# spi_usb_iic.net
KiCad netlist of a schematic drawn in EasyEDA Pro
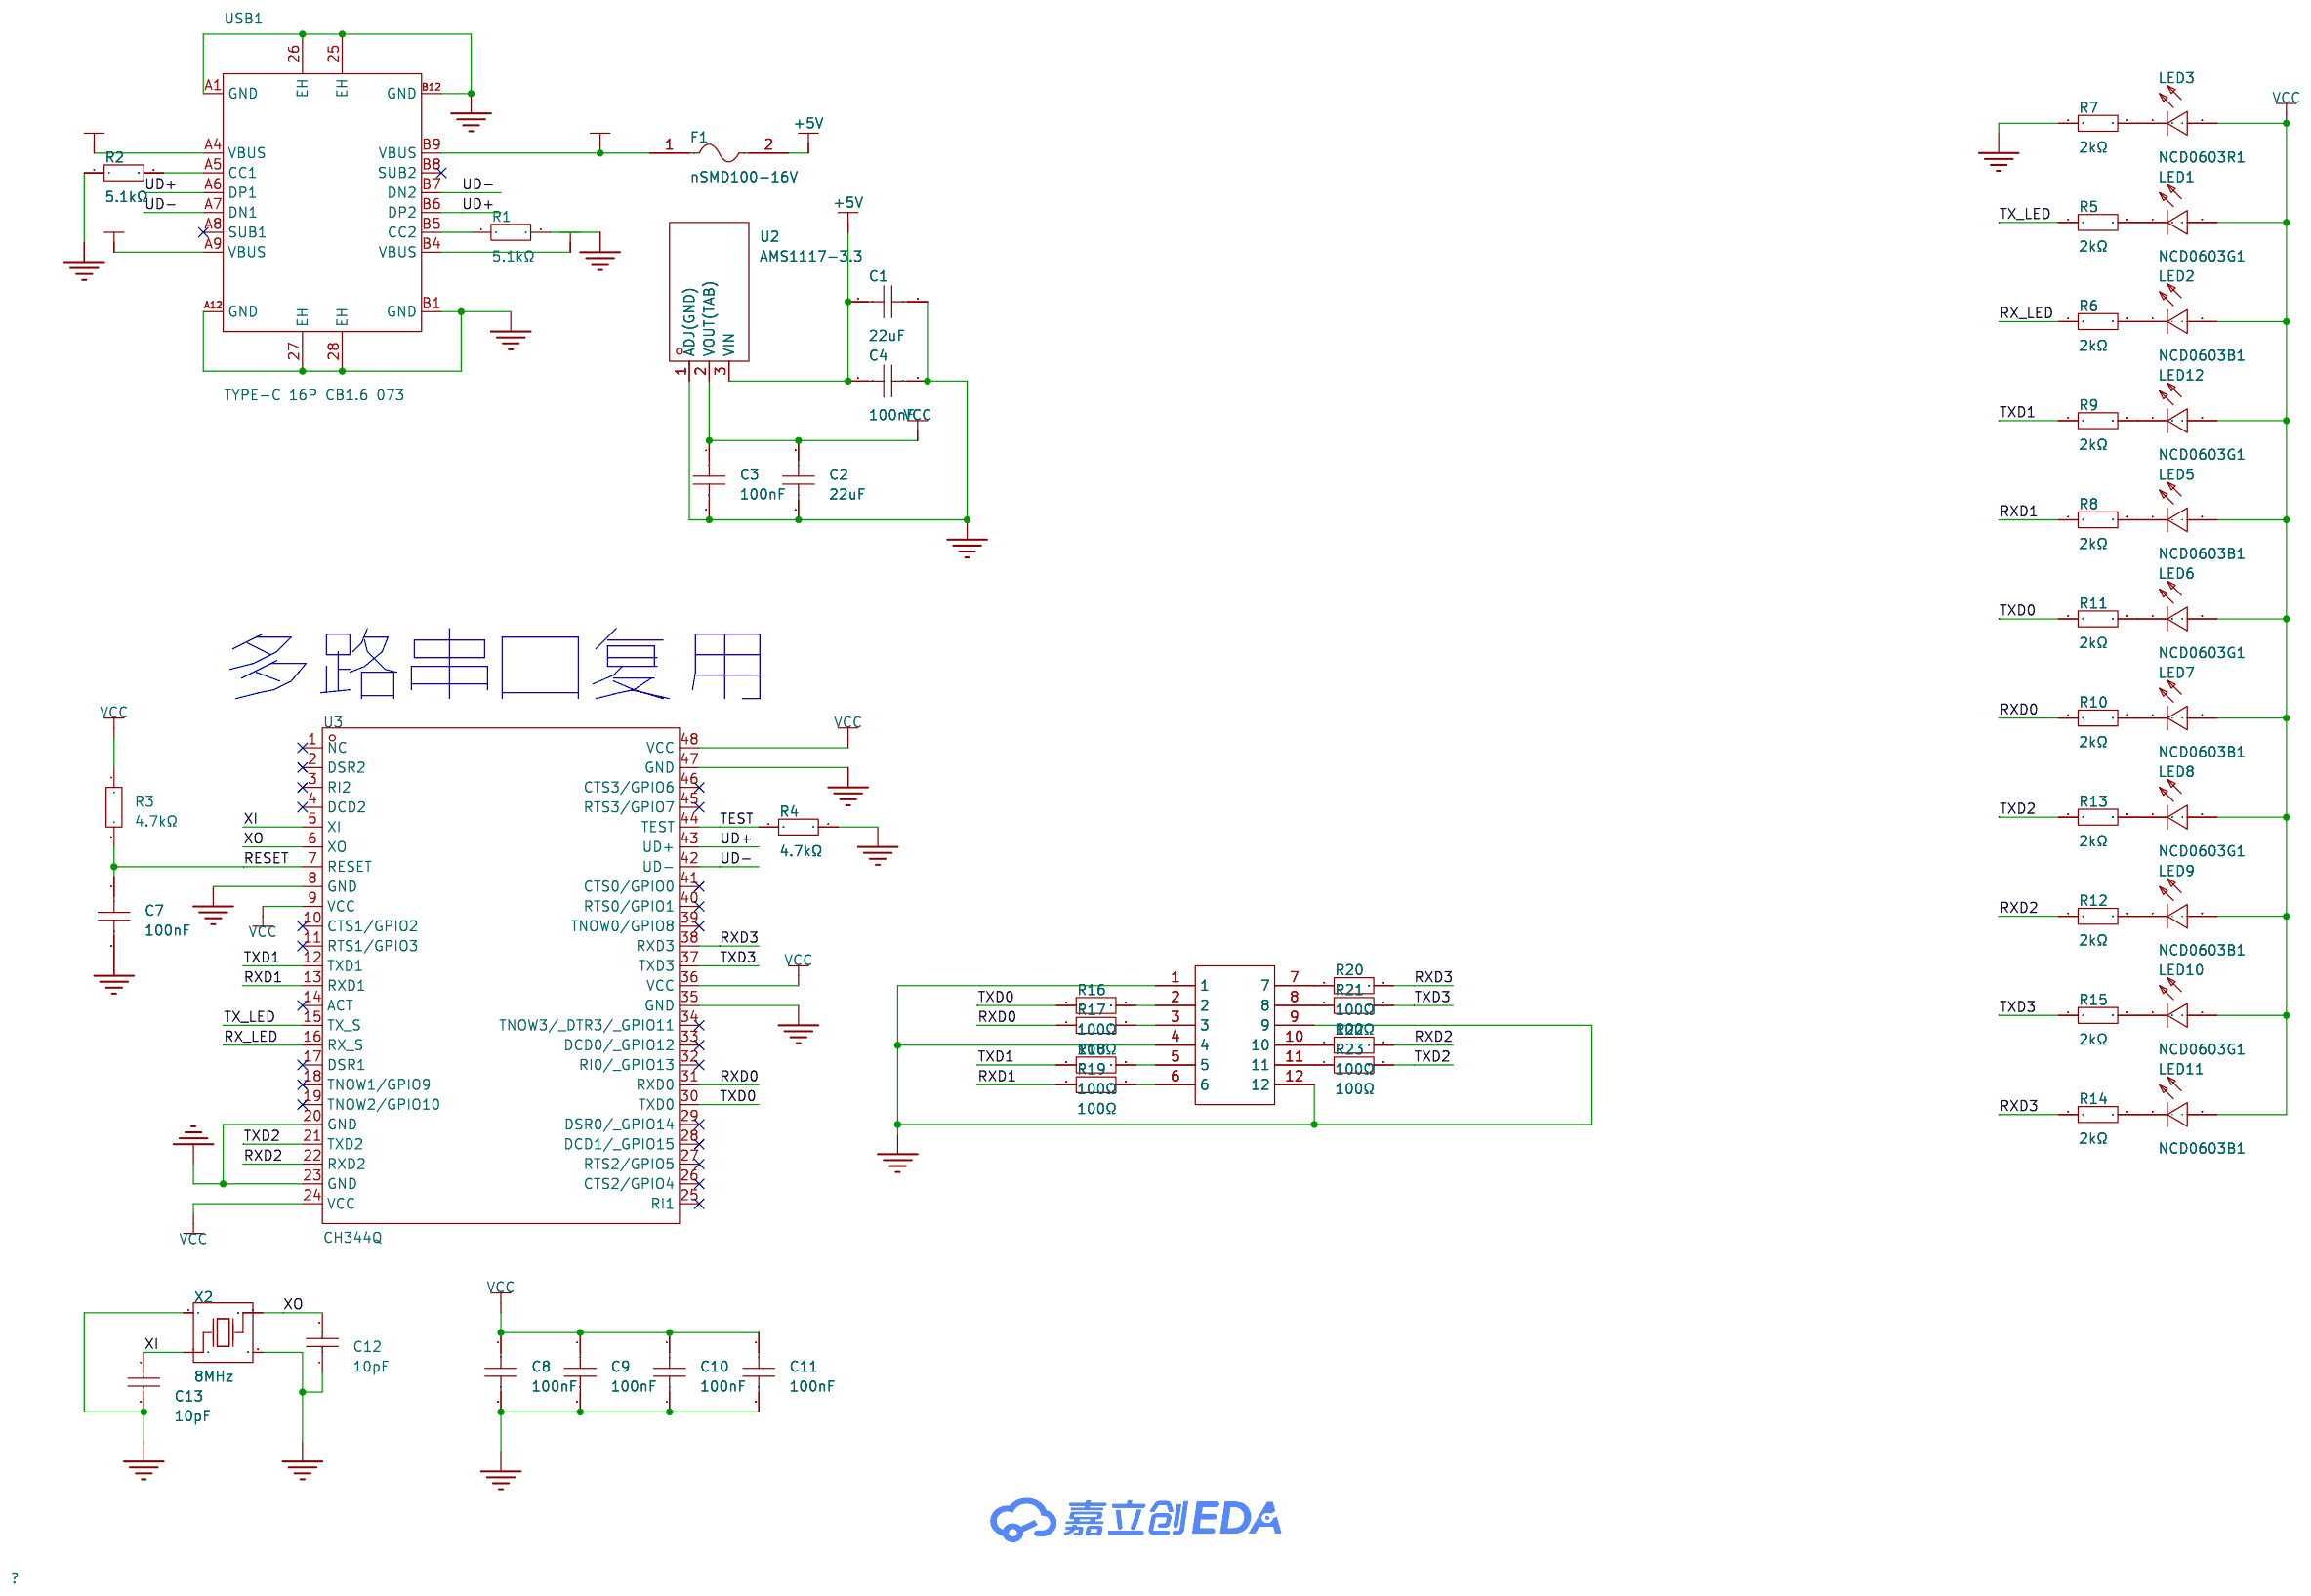
[diagram p0: USB]
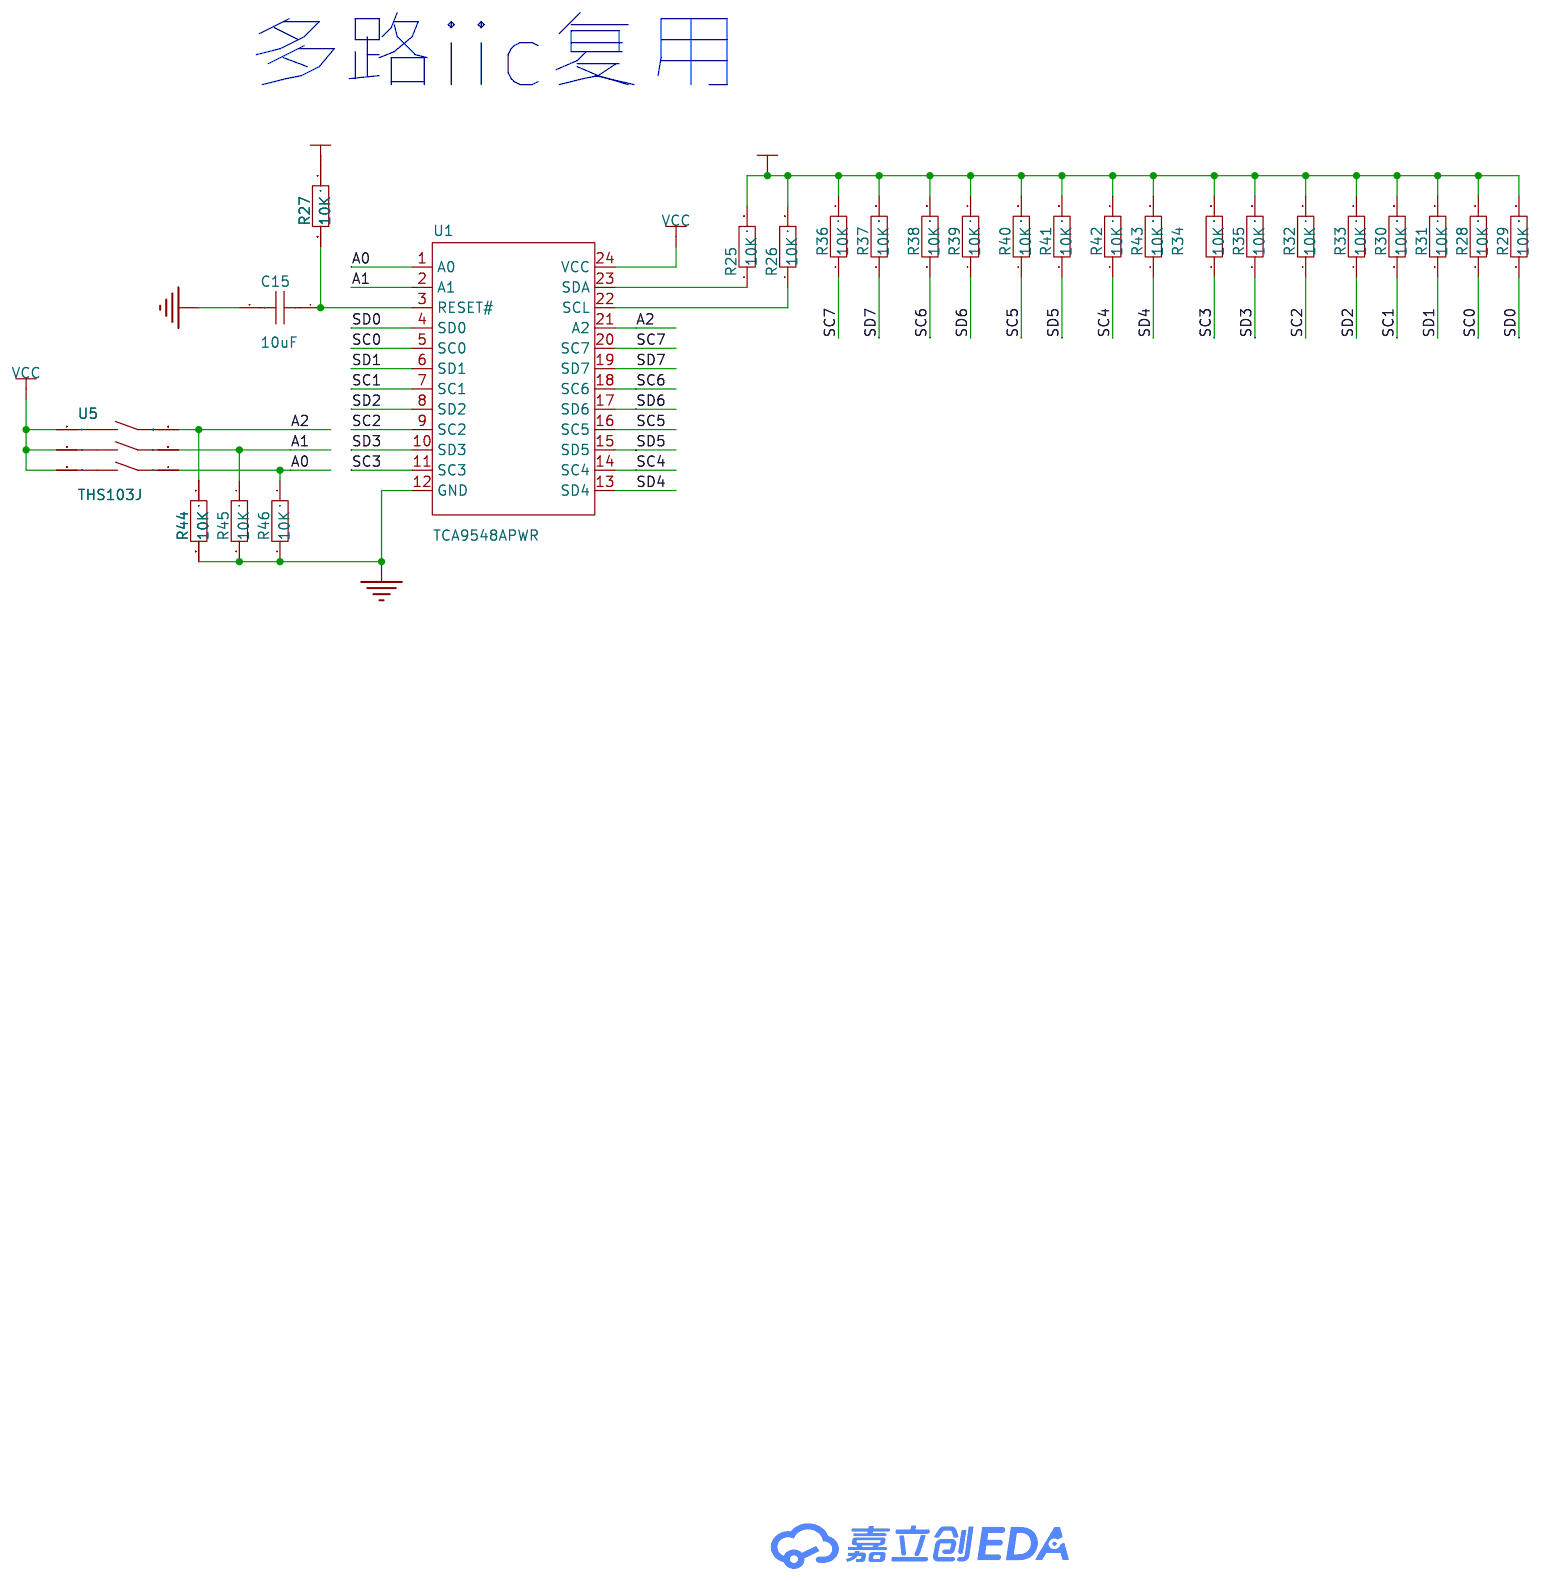
[diagram p1: IIC]
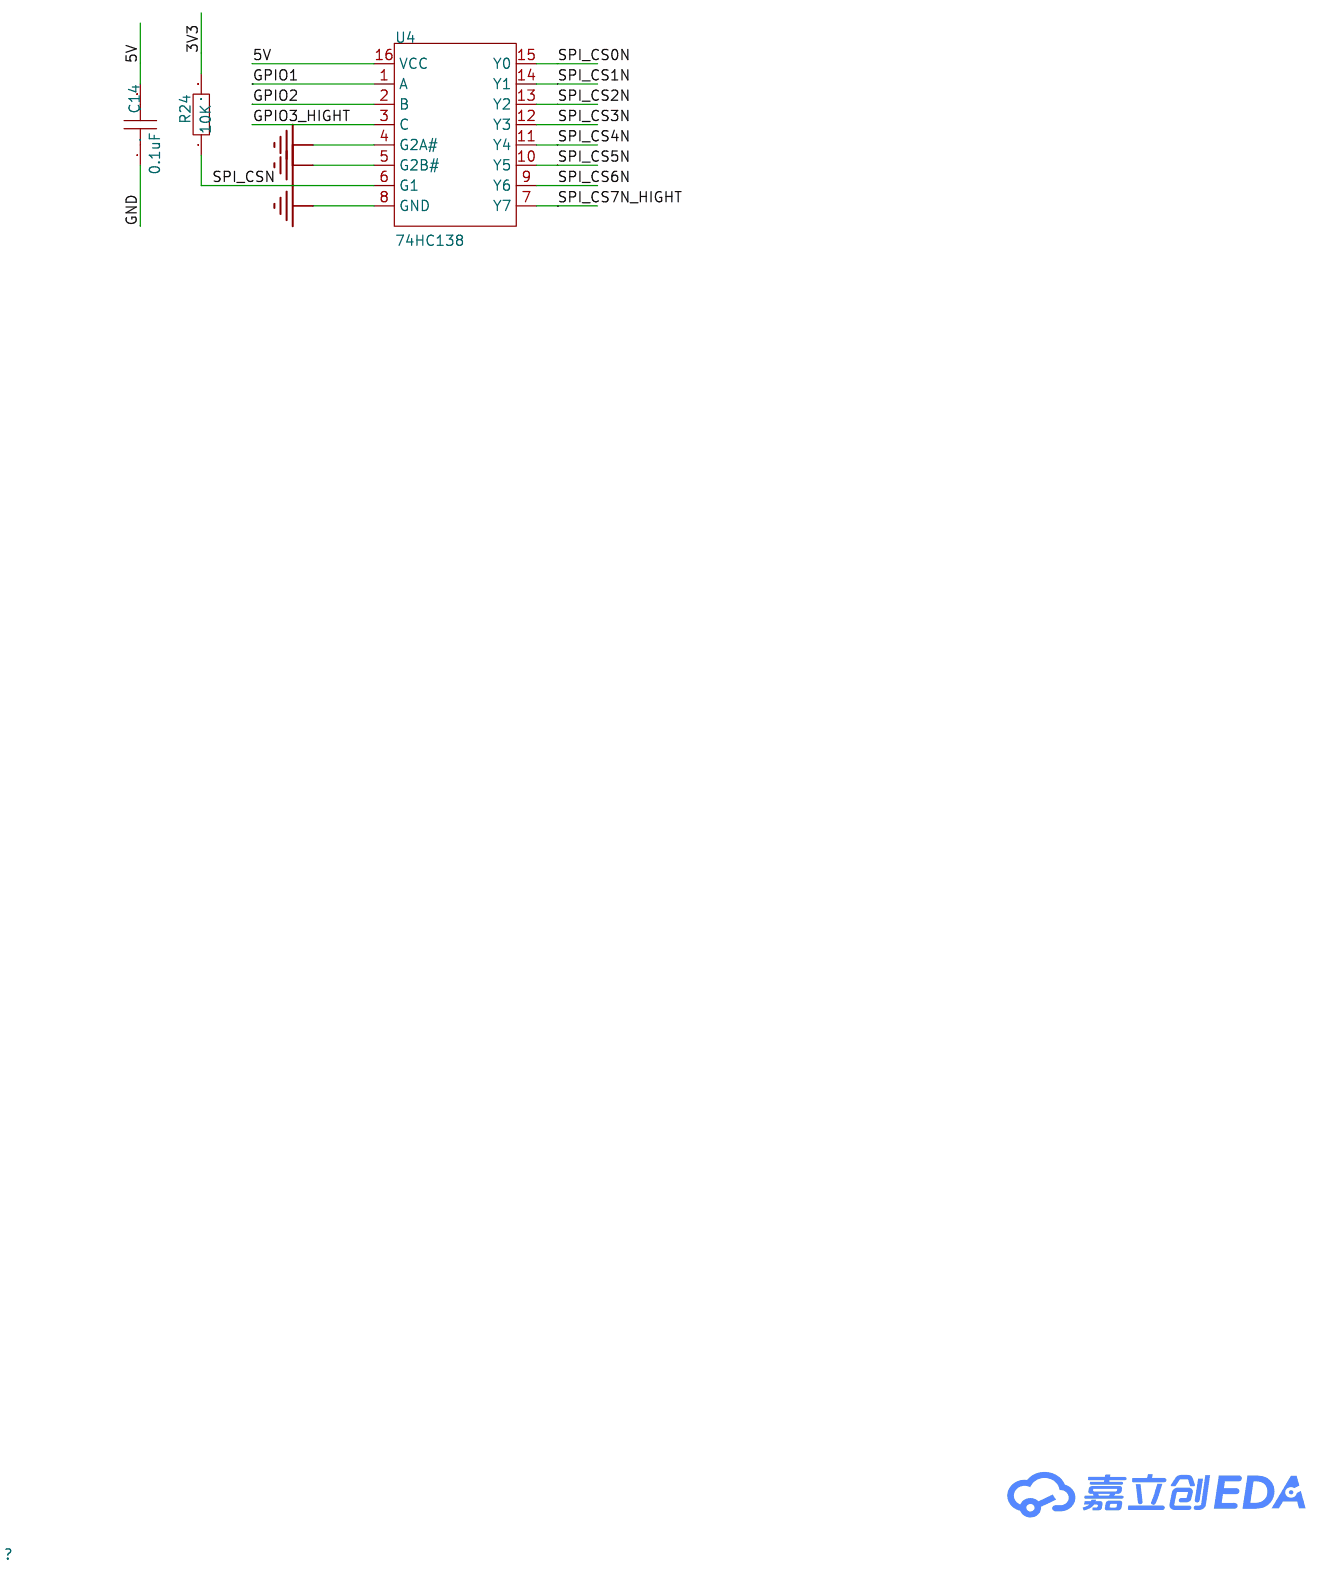
[diagram p2: SPI]

(export (version "E")
  (design (tool "Eeschema 10.0.6"))
  (components
    (comp (ref "C1")
      (value "22uF")
      (footprint "easyedapro:C0805")
      (description "容值:22uF;精度:±20%;额定电压:25V;材质(温度系数):X5R;")
      (fields
        (field (name "Manufacturer Part") "CL21A226MAQNNNE")
        (field (name "Manufacturer") "SAMSUNG(三星)")
      )
      (libsource (lib "easyedapro") (part "CL21A226MAQNNNE"))
    )
    (comp (ref "C2")
      (value "22uF")
      (footprint "easyedapro:C0805")
      (description "容值:22uF;精度:±20%;额定电压:25V;材质(温度系数):X5R;")
      (fields
        (field (name "Manufacturer Part") "CL21A226MAQNNNE")
        (field (name "Manufacturer") "SAMSUNG(三星)")
      )
      (libsource (lib "easyedapro") (part "CL21A226MAQNNNE"))
    )
    (comp (ref "C3")
      (value "100nF")
      (footprint "easyedapro:C0603")
      (description "容值:100nF;精度:±10%;额定电压:50V;材质(温度系数):X7R;")
      (fields
        (field (name "Manufacturer Part") "CL10B104KB8NNNC")
        (field (name "Manufacturer") "SAMSUNG(三星)")
      )
      (libsource (lib "easyedapro") (part "CL10B104KB8NNNC"))
    )
    (comp (ref "C4")
      (value "100nF")
      (footprint "easyedapro:C0603")
      (description "容值:100nF;精度:±10%;额定电压:50V;材质(温度系数):X7R;")
      (fields
        (field (name "Manufacturer Part") "CL10B104KB8NNNC")
        (field (name "Manufacturer") "SAMSUNG(三星)")
      )
      (libsource (lib "easyedapro") (part "CL10B104KB8NNNC"))
    )
    (comp (ref "C7")
      (value "100nF")
      (footprint "easyedapro:C0603")
      (description "容值:100nF;精度:±10%;额定电压:50V;材质(温度系数):X7R;")
      (fields
        (field (name "Manufacturer Part") "CL10B104KB8NNNC")
        (field (name "Manufacturer") "SAMSUNG(三星)")
      )
      (libsource (lib "easyedapro") (part "CL10B104KB8NNNC"))
    )
    (comp (ref "C8")
      (value "100nF")
      (footprint "easyedapro:C0603")
      (description "容值:100nF;精度:±10%;额定电压:50V;材质(温度系数):X7R;")
      (fields
        (field (name "Manufacturer Part") "CL10B104KB8NNNC")
        (field (name "Manufacturer") "SAMSUNG(三星)")
      )
      (libsource (lib "easyedapro") (part "CL10B104KB8NNNC"))
    )
    (comp (ref "C9")
      (value "100nF")
      (footprint "easyedapro:C0603")
      (description "容值:100nF;精度:±10%;额定电压:50V;材质(温度系数):X7R;")
      (fields
        (field (name "Manufacturer Part") "CL10B104KB8NNNC")
        (field (name "Manufacturer") "SAMSUNG(三星)")
      )
      (libsource (lib "easyedapro") (part "CL10B104KB8NNNC"))
    )
    (comp (ref "C10")
      (value "100nF")
      (footprint "easyedapro:C0603")
      (description "容值:100nF;精度:±10%;额定电压:50V;材质(温度系数):X7R;")
      (fields
        (field (name "Manufacturer Part") "CL10B104KB8NNNC")
        (field (name "Manufacturer") "SAMSUNG(三星)")
      )
      (libsource (lib "easyedapro") (part "CL10B104KB8NNNC"))
    )
    (comp (ref "C11")
      (value "100nF")
      (footprint "easyedapro:C0603")
      (description "容值:100nF;精度:±10%;额定电压:50V;材质(温度系数):X7R;")
      (fields
        (field (name "Manufacturer Part") "CL10B104KB8NNNC")
        (field (name "Manufacturer") "SAMSUNG(三星)")
      )
      (libsource (lib "easyedapro") (part "CL10B104KB8NNNC"))
    )
    (comp (ref "C12")
      (value "10pF")
      (footprint "easyedapro:C0603")
      (description "容值:10pF;精度:±5%;额定电压:50V;材质(温度系数):C0G;")
      (fields
        (field (name "Manufacturer Part") "CL10C100JB8NNNC")
        (field (name "Manufacturer") "SAMSUNG(三星)")
      )
      (libsource (lib "easyedapro") (part "CL10C100JB8NNNC"))
    )
    (comp (ref "C13")
      (value "10pF")
      (footprint "easyedapro:C0603")
      (description "容值:10pF;精度:±5%;额定电压:50V;材质(温度系数):C0G;")
      (fields
        (field (name "Manufacturer Part") "CL10C100JB8NNNC")
        (field (name "Manufacturer") "SAMSUNG(三星)")
      )
      (libsource (lib "easyedapro") (part "CL10C100JB8NNNC"))
    )
    (comp (ref "F1")
      (value "nSMD100-16V")
      (footprint "easyedapro:F1206")
      (description "最大电压:16V;最大电流:100A;保持电流:1A;跳闸电流:1.8A;")
      (fields (field (name "Manufacturer") "台湾陆海"))
      (libsource (lib "easyedapro") (part "nSMD100-16V"))
    )
    (comp (ref "LED1")
      (value "NCD0603G1")
      (footprint "easyedapro:LED0603-RD_1")
      (fields (field (name "Manufacturer") "国星光电"))
      (libsource (lib "easyedapro") (part "FC-D1608UGK-520D10"))
    )
    (comp (ref "LED2")
      (value "NCD0603B1")
      (footprint "easyedapro:LED0603-RD")
      (fields (field (name "Manufacturer") "国星光电"))
      (libsource (lib "easyedapro") (part "FC-DA1608BK-470H10"))
    )
    (comp (ref "LED3")
      (value "NCD0603R1")
      (footprint "easyedapro:LED0603-RD_RED")
      (fields (field (name "Manufacturer") "国星光电"))
      (libsource (lib "easyedapro") (part "FC-DA1608HRK-620D"))
    )
    (comp (ref "LED5")
      (value "NCD0603B1")
      (footprint "easyedapro:LED0603-RD")
      (fields (field (name "Manufacturer") "国星光电"))
      (libsource (lib "easyedapro") (part "FC-DA1608BK-470H10"))
    )
    (comp (ref "LED6")
      (value "NCD0603G1")
      (footprint "easyedapro:LED0603-RD_1")
      (fields (field (name "Manufacturer") "国星光电"))
      (libsource (lib "easyedapro") (part "FC-D1608UGK-520D10"))
    )
    (comp (ref "LED7")
      (value "NCD0603B1")
      (footprint "easyedapro:LED0603-RD")
      (fields (field (name "Manufacturer") "国星光电"))
      (libsource (lib "easyedapro") (part "FC-DA1608BK-470H10"))
    )
    (comp (ref "LED8")
      (value "NCD0603G1")
      (footprint "easyedapro:LED0603-RD_1")
      (fields (field (name "Manufacturer") "国星光电"))
      (libsource (lib "easyedapro") (part "FC-D1608UGK-520D10"))
    )
    (comp (ref "LED9")
      (value "NCD0603B1")
      (footprint "easyedapro:LED0603-RD")
      (fields (field (name "Manufacturer") "国星光电"))
      (libsource (lib "easyedapro") (part "FC-DA1608BK-470H10"))
    )
    (comp (ref "LED10")
      (value "NCD0603G1")
      (footprint "easyedapro:LED0603-RD_1")
      (fields (field (name "Manufacturer") "国星光电"))
      (libsource (lib "easyedapro") (part "FC-D1608UGK-520D10"))
    )
    (comp (ref "LED11")
      (value "NCD0603B1")
      (footprint "easyedapro:LED0603-RD")
      (fields (field (name "Manufacturer") "国星光电"))
      (libsource (lib "easyedapro") (part "FC-DA1608BK-470H10"))
    )
    (comp (ref "LED12")
      (value "NCD0603G1")
      (footprint "easyedapro:LED0603-RD_1")
      (fields (field (name "Manufacturer") "国星光电"))
      (libsource (lib "easyedapro") (part "FC-D1608UGK-520D10"))
    )
    (comp (ref "P2")
      (value "~")
      (footprint "easyedapro:PAD_S_2.54_2*6")
      (libsource (lib "easyedapro") (part "PAD_S_2.54_2*6"))
    )
    (comp (ref "R1")
      (value "5.1kΩ")
      (footprint "easyedapro:R0603")
      (description "电阻类型:厚膜电阻;阻值:5.1kΩ;精度:±1%;功率:100mW;最大工作电压:75V;温度系数:±100ppm/°C;")
      (fields
        (field (name "Manufacturer Part") "0603WAF5101T5E")
        (field (name "Manufacturer") "UNI-ROYAL(厚声)")
      )
      (libsource (lib "easyedapro") (part "0603WAF5101T5E"))
    )
    (comp (ref "R2")
      (value "5.1kΩ")
      (footprint "easyedapro:R0603")
      (description "电阻类型:厚膜电阻;阻值:5.1kΩ;精度:±1%;功率:100mW;最大工作电压:75V;温度系数:±100ppm/°C;")
      (fields
        (field (name "Manufacturer Part") "0603WAF5101T5E")
        (field (name "Manufacturer") "UNI-ROYAL(厚声)")
      )
      (libsource (lib "easyedapro") (part "0603WAF5101T5E"))
    )
    (comp (ref "R3")
      (value "4.7kΩ")
      (footprint "easyedapro:R0603")
      (description "电阻类型:厚膜电阻;阻值:4.7kΩ;精度:±1%;功率:100mW;最大工作电压:75V;温度系数:±100ppm/°C;")
      (fields
        (field (name "Manufacturer Part") "0603WAF4701T5E")
        (field (name "Manufacturer") "UNI-ROYAL(厚声)")
      )
      (libsource (lib "easyedapro") (part "0603WAF4701T5E"))
    )
    (comp (ref "R4")
      (value "4.7kΩ")
      (footprint "easyedapro:R0603")
      (description "电阻类型:厚膜电阻;阻值:4.7kΩ;精度:±1%;功率:100mW;最大工作电压:75V;温度系数:±100ppm/°C;")
      (fields
        (field (name "Manufacturer Part") "0603WAF4701T5E")
        (field (name "Manufacturer") "UNI-ROYAL(厚声)")
      )
      (libsource (lib "easyedapro") (part "0603WAF4701T5E"))
    )
    (comp (ref "R5")
      (value "2kΩ")
      (footprint "easyedapro:R0603")
      (description "电阻类型:厚膜电阻;阻值:2kΩ;精度:±1%;功率:100mW;最大工作电压:75V;温度系数:±100ppm/°C;")
      (fields
        (field (name "Manufacturer Part") "0603WAF2001T5E")
        (field (name "Manufacturer") "UNI-ROYAL(厚声)")
      )
      (libsource (lib "easyedapro") (part "0603WAF2001T5E"))
    )
    (comp (ref "R6")
      (value "2kΩ")
      (footprint "easyedapro:R0603")
      (description "电阻类型:厚膜电阻;阻值:2kΩ;精度:±1%;功率:100mW;最大工作电压:75V;温度系数:±100ppm/°C;")
      (fields
        (field (name "Manufacturer Part") "0603WAF2001T5E")
        (field (name "Manufacturer") "UNI-ROYAL(厚声)")
      )
      (libsource (lib "easyedapro") (part "0603WAF2001T5E"))
    )
    (comp (ref "R7")
      (value "2kΩ")
      (footprint "easyedapro:R0603")
      (description "电阻类型:厚膜电阻;阻值:2kΩ;精度:±1%;功率:100mW;最大工作电压:75V;温度系数:±100ppm/°C;")
      (fields
        (field (name "Manufacturer Part") "0603WAF2001T5E")
        (field (name "Manufacturer") "UNI-ROYAL(厚声)")
      )
      (libsource (lib "easyedapro") (part "0603WAF2001T5E"))
    )
    (comp (ref "R8")
      (value "2kΩ")
      (footprint "easyedapro:R0603")
      (description "电阻类型:厚膜电阻;阻值:2kΩ;精度:±1%;功率:100mW;最大工作电压:75V;温度系数:±100ppm/°C;")
      (fields
        (field (name "Manufacturer Part") "0603WAF2001T5E")
        (field (name "Manufacturer") "UNI-ROYAL(厚声)")
      )
      (libsource (lib "easyedapro") (part "0603WAF2001T5E"))
    )
    (comp (ref "R9")
      (value "2kΩ")
      (footprint "easyedapro:R0603")
      (description "电阻类型:厚膜电阻;阻值:2kΩ;精度:±1%;功率:100mW;最大工作电压:75V;温度系数:±100ppm/°C;")
      (fields
        (field (name "Manufacturer Part") "0603WAF2001T5E")
        (field (name "Manufacturer") "UNI-ROYAL(厚声)")
      )
      (libsource (lib "easyedapro") (part "0603WAF2001T5E"))
    )
    (comp (ref "R10")
      (value "2kΩ")
      (footprint "easyedapro:R0603")
      (description "电阻类型:厚膜电阻;阻值:2kΩ;精度:±1%;功率:100mW;最大工作电压:75V;温度系数:±100ppm/°C;")
      (fields
        (field (name "Manufacturer Part") "0603WAF2001T5E")
        (field (name "Manufacturer") "UNI-ROYAL(厚声)")
      )
      (libsource (lib "easyedapro") (part "0603WAF2001T5E"))
    )
    (comp (ref "R11")
      (value "2kΩ")
      (footprint "easyedapro:R0603")
      (description "电阻类型:厚膜电阻;阻值:2kΩ;精度:±1%;功率:100mW;最大工作电压:75V;温度系数:±100ppm/°C;")
      (fields
        (field (name "Manufacturer Part") "0603WAF2001T5E")
        (field (name "Manufacturer") "UNI-ROYAL(厚声)")
      )
      (libsource (lib "easyedapro") (part "0603WAF2001T5E"))
    )
    (comp (ref "R12")
      (value "2kΩ")
      (footprint "easyedapro:R0603")
      (description "电阻类型:厚膜电阻;阻值:2kΩ;精度:±1%;功率:100mW;最大工作电压:75V;温度系数:±100ppm/°C;")
      (fields
        (field (name "Manufacturer Part") "0603WAF2001T5E")
        (field (name "Manufacturer") "UNI-ROYAL(厚声)")
      )
      (libsource (lib "easyedapro") (part "0603WAF2001T5E"))
    )
    (comp (ref "R13")
      (value "2kΩ")
      (footprint "easyedapro:R0603")
      (description "电阻类型:厚膜电阻;阻值:2kΩ;精度:±1%;功率:100mW;最大工作电压:75V;温度系数:±100ppm/°C;")
      (fields
        (field (name "Manufacturer Part") "0603WAF2001T5E")
        (field (name "Manufacturer") "UNI-ROYAL(厚声)")
      )
      (libsource (lib "easyedapro") (part "0603WAF2001T5E"))
    )
    (comp (ref "R14")
      (value "2kΩ")
      (footprint "easyedapro:R0603")
      (description "电阻类型:厚膜电阻;阻值:2kΩ;精度:±1%;功率:100mW;最大工作电压:75V;温度系数:±100ppm/°C;")
      (fields
        (field (name "Manufacturer Part") "0603WAF2001T5E")
        (field (name "Manufacturer") "UNI-ROYAL(厚声)")
      )
      (libsource (lib "easyedapro") (part "0603WAF2001T5E"))
    )
    (comp (ref "R15")
      (value "2kΩ")
      (footprint "easyedapro:R0603")
      (description "电阻类型:厚膜电阻;阻值:2kΩ;精度:±1%;功率:100mW;最大工作电压:75V;温度系数:±100ppm/°C;")
      (fields
        (field (name "Manufacturer Part") "0603WAF2001T5E")
        (field (name "Manufacturer") "UNI-ROYAL(厚声)")
      )
      (libsource (lib "easyedapro") (part "0603WAF2001T5E"))
    )
    (comp (ref "R16")
      (value "100Ω")
      (footprint "easyedapro:R0603")
      (description "电阻类型:厚膜电阻;阻值:100Ω;精度:±1%;功率:100mW;最大工作电压:75V;温度系数:±200ppm/°C;")
      (fields
        (field (name "Manufacturer Part") "0603WAF1000T5E")
        (field (name "Manufacturer") "UNI-ROYAL(厚声)")
      )
      (libsource (lib "easyedapro") (part "0603WAF1000T5E"))
    )
    (comp (ref "R17")
      (value "100Ω")
      (footprint "easyedapro:R0603")
      (description "电阻类型:厚膜电阻;阻值:100Ω;精度:±1%;功率:100mW;最大工作电压:75V;温度系数:±200ppm/°C;")
      (fields
        (field (name "Manufacturer Part") "0603WAF1000T5E")
        (field (name "Manufacturer") "UNI-ROYAL(厚声)")
      )
      (libsource (lib "easyedapro") (part "0603WAF1000T5E"))
    )
    (comp (ref "R18")
      (value "100Ω")
      (footprint "easyedapro:R0603")
      (description "电阻类型:厚膜电阻;阻值:100Ω;精度:±1%;功率:100mW;最大工作电压:75V;温度系数:±200ppm/°C;")
      (fields
        (field (name "Manufacturer Part") "0603WAF1000T5E")
        (field (name "Manufacturer") "UNI-ROYAL(厚声)")
      )
      (libsource (lib "easyedapro") (part "0603WAF1000T5E"))
    )
    (comp (ref "R19")
      (value "100Ω")
      (footprint "easyedapro:R0603")
      (description "电阻类型:厚膜电阻;阻值:100Ω;精度:±1%;功率:100mW;最大工作电压:75V;温度系数:±200ppm/°C;")
      (fields
        (field (name "Manufacturer Part") "0603WAF1000T5E")
        (field (name "Manufacturer") "UNI-ROYAL(厚声)")
      )
      (libsource (lib "easyedapro") (part "0603WAF1000T5E"))
    )
    (comp (ref "R20")
      (value "100Ω")
      (footprint "easyedapro:R0603")
      (description "电阻类型:厚膜电阻;阻值:100Ω;精度:±1%;功率:100mW;最大工作电压:75V;温度系数:±200ppm/°C;")
      (fields
        (field (name "Manufacturer Part") "0603WAF1000T5E")
        (field (name "Manufacturer") "UNI-ROYAL(厚声)")
      )
      (libsource (lib "easyedapro") (part "0603WAF1000T5E"))
    )
    (comp (ref "R21")
      (value "100Ω")
      (footprint "easyedapro:R0603")
      (description "电阻类型:厚膜电阻;阻值:100Ω;精度:±1%;功率:100mW;最大工作电压:75V;温度系数:±200ppm/°C;")
      (fields
        (field (name "Manufacturer Part") "0603WAF1000T5E")
        (field (name "Manufacturer") "UNI-ROYAL(厚声)")
      )
      (libsource (lib "easyedapro") (part "0603WAF1000T5E"))
    )
    (comp (ref "R22")
      (value "100Ω")
      (footprint "easyedapro:R0603")
      (description "电阻类型:厚膜电阻;阻值:100Ω;精度:±1%;功率:100mW;最大工作电压:75V;温度系数:±200ppm/°C;")
      (fields
        (field (name "Manufacturer Part") "0603WAF1000T5E")
        (field (name "Manufacturer") "UNI-ROYAL(厚声)")
      )
      (libsource (lib "easyedapro") (part "0603WAF1000T5E"))
    )
    (comp (ref "R23")
      (value "100Ω")
      (footprint "easyedapro:R0603")
      (description "电阻类型:厚膜电阻;阻值:100Ω;精度:±1%;功率:100mW;最大工作电压:75V;温度系数:±200ppm/°C;")
      (fields
        (field (name "Manufacturer Part") "0603WAF1000T5E")
        (field (name "Manufacturer") "UNI-ROYAL(厚声)")
      )
      (libsource (lib "easyedapro") (part "0603WAF1000T5E"))
    )
    (comp (ref "U2")
      (value "AMS1117-3.3")
      (footprint "easyedapro:SOT-89_L4.5-W2.5-P1.50-LS4.2-BR")
      (description "输出类型:固定;工作电压:18V;输出电压:3.3V;输出电流:1A;电源纹波抑制比(PSRR):60dB@(120Hz);输出极性:正极;")
      (fields (field (name "Manufacturer") "UMW(友台半导体)"))
      (libsource (lib "easyedapro") (part "AMS1117-3.3_C347256"))
    )
    (comp (ref "U3")
      (value "CH344Q")
      (footprint "easyedapro:LQFP-48_L7.0-W7.0-P0.50-LS9.0-BL")
      (description "应用功能:USB转UART；USB转RS485；USB转RS422；USB转RS232;接口协议:USB 3.0;通道数:4;数据速率:6Mbps;")
      (fields (field (name "Manufacturer") "WCH(南京沁恒)"))
      (libsource (lib "easyedapro") (part "CH344Q_C2988084"))
    )
    (comp (ref "USB1")
      (value "TYPE-C 16P CB1.6 073")
      (footprint "easyedapro:USB-C-SMD_SHOU_TYPE-C-16P-CB1.6")
      (description "连接器类型:Type-C;标准:USB 3.1;公母:母;安装方式:沉板;触点数量:16P;端口数量:1;额定电流 - 电源:3A;工作温度范围:-25°C~+85°C;")
      (fields (field (name "Manufacturer") "SHOU HAN(首韩)"))
      (libsource (lib "easyedapro") (part "TYPE-C 16P CB1.6 073"))
    )
    (comp (ref "X2")
      (value "8MHz")
      (footprint "easyedapro:CRYSTAL-SMD_4P-L3.2-W2.5-BL")
      (description "晶振类型:贴片晶振;频率:8MHz;常温频差:±10ppm;负载电容:10pF;频率稳定度(全温):±15ppm;")
      (fields (field (name "Manufacturer Part") "TAXM8M4RDBCCT2T") (field (name "Manufacturer") "YJX(雅晶鑫)"))
      (libsource (lib "easyedapro") (part "TAXM8M4RDBCCT2T"))
    )
    (comp (ref "C15")
      (value "10uF")
      (footprint "easyedapro:C0603")
      (libsource (lib "easyedapro") (part "CapAcitance"))
    )
    (comp (ref "R25") (value "10K") (footprint "easyedapro:R0603") (libsource (lib "easyedapro") (part "电阻")))
    (comp (ref "R26") (value "10K") (footprint "easyedapro:R0603") (libsource (lib "easyedapro") (part "电阻")))
    (comp (ref "R27") (value "10K") (footprint "easyedapro:R0603") (libsource (lib "easyedapro") (part "电阻")))
    (comp (ref "R28") (value "10K") (footprint "easyedapro:R0603") (libsource (lib "easyedapro") (part "电阻")))
    (comp (ref "R29") (value "10K") (footprint "easyedapro:R0603") (libsource (lib "easyedapro") (part "电阻")))
    (comp (ref "R30") (value "10K") (footprint "easyedapro:R0603") (libsource (lib "easyedapro") (part "电阻")))
    (comp (ref "R31") (value "10K") (footprint "easyedapro:R0603") (libsource (lib "easyedapro") (part "电阻")))
    (comp (ref "R32") (value "10K") (footprint "easyedapro:R0603") (libsource (lib "easyedapro") (part "电阻")))
    (comp (ref "R33") (value "10K") (footprint "easyedapro:R0603") (libsource (lib "easyedapro") (part "电阻")))
    (comp (ref "R34") (value "10K") (footprint "easyedapro:R0603") (libsource (lib "easyedapro") (part "电阻")))
    (comp (ref "R35") (value "10K") (footprint "easyedapro:R0603") (libsource (lib "easyedapro") (part "电阻")))
    (comp (ref "R36") (value "10K") (footprint "easyedapro:R0603") (libsource (lib "easyedapro") (part "电阻")))
    (comp (ref "R37") (value "10K") (footprint "easyedapro:R0603") (libsource (lib "easyedapro") (part "电阻")))
    (comp (ref "R38") (value "10K") (footprint "easyedapro:R0603") (libsource (lib "easyedapro") (part "电阻")))
    (comp (ref "R39") (value "10K") (footprint "easyedapro:R0603") (libsource (lib "easyedapro") (part "电阻")))
    (comp (ref "R40") (value "10K") (footprint "easyedapro:R0603") (libsource (lib "easyedapro") (part "电阻")))
    (comp (ref "R41") (value "10K") (footprint "easyedapro:R0603") (libsource (lib "easyedapro") (part "电阻")))
    (comp (ref "R42") (value "10K") (footprint "easyedapro:R0603") (libsource (lib "easyedapro") (part "电阻")))
    (comp (ref "R43") (value "10K") (footprint "easyedapro:R0603") (libsource (lib "easyedapro") (part "电阻")))
    (comp (ref "R44") (value "10K") (footprint "easyedapro:R0603") (libsource (lib "easyedapro") (part "电阻")))
    (comp (ref "R45") (value "10K") (footprint "easyedapro:R0603") (libsource (lib "easyedapro") (part "电阻")))
    (comp (ref "R46") (value "10K") (footprint "easyedapro:R0603") (libsource (lib "easyedapro") (part "电阻")))
    (comp (ref "U1")
      (value "TCA9548APWR")
      (footprint "easyedapro:TSSOP-24_L7.8-W4.4-P0.65-LS6.4-BL")
      (description "TCA9548A 具有复位和电压转换的 8 通道、1.65V 至 5.5V I2C/SMBus 开关")
      (fields (field (name "Manufacturer") "TI(德州仪器)"))
      (libsource (lib "easyedapro") (part "TCA9548APWR"))
    )
    (comp (ref "U5")
      (value "THS103J")
      (footprint "easyedapro:SW-SMD_6P-L5.4-W5.4-P1.27-LS5.6")
      (description "类型:平拨,凹槽式;电路结构:单刀单掷;开关位数:3位;额定电流:25mA;额定电压:24V;使用寿命:3千次;颜色:黑色;")
      (fields (field (name "Manufacturer") "ROCPU Switches(台普)"))
      (libsource (lib "easyedapro") (part "THS103J"))
    )
    (comp (ref "C14")
      (value "0.1uF")
      (footprint "easyedapro:C0603")
      (libsource (lib "easyedapro") (part "CapAcitance"))
    )
    (comp (ref "R24") (value "10K") (footprint "easyedapro:R0603") (libsource (lib "easyedapro") (part "电阻")))
    (comp (ref "U4")
      (value "74HC138")
      (footprint "easyedapro:SOP-16_L10.0-W3.9-P1.27-LS6.0-BL")
      (description "供电电压:2V~6V;线路数:3~8;灌电流(IOL):5.2mA;拉电流(IOH):5.2mA;")
      (fields (field (name "Manufacturer") "GR(国睿)"))
      (libsource (lib "easyedapro") (part "74HC138_C18164491"))
    )
  )
  (nets
    (net (code "1") (name "+5V") (class "Default")
      (node (ref "C1") (pin "1") (pinfunction "1_1") (pintype "unspecified"))
      (node (ref "C4") (pin "1") (pinfunction "1_1") (pintype "unspecified"))
      (node (ref "F1") (pin "2") (pinfunction "2_2") (pintype "unspecified"))
      (node (ref "U2") (pin "3") (pinfunction "VIN_3") (pintype "unspecified"))
    )
    (net (code "2") (name "3V3") (class "Default")
      (node (ref "R24") (pin "2") (pinfunction "2_2") (pintype "input"))
      (node (ref "R25") (pin "2") (pinfunction "2_2") (pintype "input"))
      (node (ref "R26") (pin "2") (pinfunction "2_2") (pintype "input"))
      (node (ref "R27") (pin "1") (pinfunction "1_1") (pintype "input"))
      (node (ref "R28") (pin "2") (pinfunction "2_2") (pintype "input"))
      (node (ref "R29") (pin "2") (pinfunction "2_2") (pintype "input"))
      (node (ref "R30") (pin "2") (pinfunction "2_2") (pintype "input"))
      (node (ref "R31") (pin "2") (pinfunction "2_2") (pintype "input"))
      (node (ref "R32") (pin "2") (pinfunction "2_2") (pintype "input"))
      (node (ref "R33") (pin "2") (pinfunction "2_2") (pintype "input"))
      (node (ref "R34") (pin "2") (pinfunction "2_2") (pintype "input"))
      (node (ref "R35") (pin "2") (pinfunction "2_2") (pintype "input"))
      (node (ref "R36") (pin "2") (pinfunction "2_2") (pintype "input"))
      (node (ref "R37") (pin "2") (pinfunction "2_2") (pintype "input"))
      (node (ref "R38") (pin "2") (pinfunction "2_2") (pintype "input"))
      (node (ref "R39") (pin "2") (pinfunction "2_2") (pintype "input"))
      (node (ref "R40") (pin "2") (pinfunction "2_2") (pintype "input"))
      (node (ref "R41") (pin "2") (pinfunction "2_2") (pintype "input"))
      (node (ref "R42") (pin "2") (pinfunction "2_2") (pintype "input"))
      (node (ref "R43") (pin "2") (pinfunction "2_2") (pintype "input"))
    )
    (net (code "3") (name "5V") (class "Default")
      (node (ref "C14") (pin "2") (pinfunction "2_2") (pintype "input"))
      (node (ref "U4") (pin "16") (pinfunction "VCC_16") (pintype "unspecified"))
    )
    (net (code "4") (name "A0") (class "Default")
      (node (ref "R46") (pin "1") (pinfunction "1_1") (pintype "input"))
      (node (ref "U1") (pin "1") (pinfunction "A0_1") (pintype "unspecified"))
      (node (ref "U5") (pin "4") (pinfunction "4_4") (pintype "unspecified"))
    )
    (net (code "5") (name "A1") (class "Default")
      (node (ref "R45") (pin "1") (pinfunction "1_1") (pintype "input"))
      (node (ref "U1") (pin "2") (pinfunction "A1_2") (pintype "unspecified"))
      (node (ref "U5") (pin "5") (pinfunction "5_5") (pintype "unspecified"))
    )
    (net (code "6") (name "A2") (class "Default")
      (node (ref "R44") (pin "1") (pinfunction "1_1") (pintype "input"))
      (node (ref "U1") (pin "21") (pinfunction "A2_21") (pintype "unspecified"))
      (node (ref "U5") (pin "6") (pinfunction "6_6") (pintype "unspecified"))
    )
    (net (code "7") (name "GND") (class "Default")
      (node (ref "C1") (pin "2") (pinfunction "2_2") (pintype "unspecified"))
      (node (ref "C10") (pin "2") (pinfunction "2_2") (pintype "unspecified"))
      (node (ref "C11") (pin "2") (pinfunction "2_2") (pintype "unspecified"))
      (node (ref "C12") (pin "2") (pinfunction "2_2") (pintype "input"))
      (node (ref "C13") (pin "2") (pinfunction "2_2") (pintype "input"))
      (node (ref "C14") (pin "1") (pinfunction "1_1") (pintype "input"))
      (node (ref "C15") (pin "2") (pinfunction "2_2") (pintype "input"))
      (node (ref "C2") (pin "1") (pinfunction "1_1") (pintype "unspecified"))
      (node (ref "C3") (pin "2") (pinfunction "2_2") (pintype "unspecified"))
      (node (ref "C4") (pin "2") (pinfunction "2_2") (pintype "unspecified"))
      (node (ref "C7") (pin "2") (pinfunction "2_2") (pintype "unspecified"))
      (node (ref "C8") (pin "2") (pinfunction "2_2") (pintype "unspecified"))
      (node (ref "C9") (pin "2") (pinfunction "2_2") (pintype "unspecified"))
      (node (ref "P2") (pin "1") (pinfunction "1_1") (pintype "input"))
      (node (ref "P2") (pin "12") (pinfunction "12_12") (pintype "input"))
      (node (ref "P2") (pin "4") (pinfunction "4_4") (pintype "input"))
      (node (ref "P2") (pin "9") (pinfunction "9_9") (pintype "input"))
      (node (ref "R1") (pin "2") (pinfunction "2_2") (pintype "input"))
      (node (ref "R2") (pin "1") (pinfunction "1_1") (pintype "input"))
      (node (ref "R4") (pin "1") (pinfunction "1_1") (pintype "input"))
      (node (ref "R44") (pin "2") (pinfunction "2_2") (pintype "input"))
      (node (ref "R45") (pin "2") (pinfunction "2_2") (pintype "input"))
      (node (ref "R46") (pin "2") (pinfunction "2_2") (pintype "input"))
      (node (ref "R7") (pin "1") (pinfunction "1_1") (pintype "input"))
      (node (ref "U1") (pin "12") (pinfunction "GND_12") (pintype "unspecified"))
      (node (ref "U2") (pin "1") (pinfunction "ADJ(GND)_1") (pintype "unspecified"))
      (node (ref "U3") (pin "20") (pinfunction "GND_20") (pintype "unspecified"))
      (node (ref "U3") (pin "23") (pinfunction "GND_23") (pintype "unspecified"))
      (node (ref "U3") (pin "35") (pinfunction "GND_35") (pintype "unspecified"))
      (node (ref "U3") (pin "47") (pinfunction "GND_47") (pintype "unspecified"))
      (node (ref "U3") (pin "8") (pinfunction "GND_8") (pintype "unspecified"))
      (node (ref "U4") (pin "4") (pinfunction "G2A#_4") (pintype "unspecified"))
      (node (ref "U4") (pin "5") (pinfunction "G2B#_5") (pintype "unspecified"))
      (node (ref "U4") (pin "8") (pinfunction "GND_8") (pintype "unspecified"))
      (node (ref "USB1") (pin "25") (pinfunction "EH_25") (pintype "unspecified"))
      (node (ref "USB1") (pin "26") (pinfunction "EH_26") (pintype "unspecified"))
      (node (ref "USB1") (pin "27") (pinfunction "EH_27") (pintype "unspecified"))
      (node (ref "USB1") (pin "28") (pinfunction "EH_28") (pintype "unspecified"))
      (node (ref "USB1") (pin "A1") (pinfunction "GND_A1") (pintype "unspecified"))
      (node (ref "USB1") (pin "A12") (pinfunction "GND_A12") (pintype "unspecified"))
      (node (ref "USB1") (pin "B1") (pinfunction "GND_B1") (pintype "unspecified"))
      (node (ref "USB1") (pin "B12") (pinfunction "GND_B12") (pintype "unspecified"))
      (node (ref "X2") (pin "2") (pinfunction "2_2") (pintype "input"))
      (node (ref "X2") (pin "4") (pinfunction "4_4") (pintype "input"))
    )
    (net (code "8") (name "GPIO1") (class "Default")
      (node (ref "U4") (pin "1") (pinfunction "A_1") (pintype "unspecified"))
    )
    (net (code "9") (name "GPIO2") (class "Default")
      (node (ref "U4") (pin "2") (pinfunction "B_2") (pintype "unspecified"))
    )
    (net (code "10") (name "GPIO3_HIGHT") (class "Default")
      (node (ref "U4") (pin "3") (pinfunction "C_3") (pintype "unspecified"))
    )
    (net (code "11") (name "Net-(LED1-K)") (class "Default")
      (node (ref "LED1") (pin "1") (pinfunction "K_1") (pintype "input"))
      (node (ref "R5") (pin "2") (pinfunction "2_2") (pintype "input"))
    )
    (net (code "12") (name "Net-(LED2--)") (class "Default")
      (node (ref "LED2") (pin "1") (pinfunction "-_1") (pintype "input"))
      (node (ref "R6") (pin "2") (pinfunction "2_2") (pintype "input"))
    )
    (net (code "13") (name "Net-(LED3-K)") (class "Default")
      (node (ref "LED3") (pin "1") (pinfunction "K_1") (pintype "input"))
      (node (ref "R7") (pin "2") (pinfunction "2_2") (pintype "input"))
    )
    (net (code "14") (name "Net-(LED5--)") (class "Default")
      (node (ref "LED5") (pin "1") (pinfunction "-_1") (pintype "input"))
      (node (ref "R8") (pin "2") (pinfunction "2_2") (pintype "input"))
    )
    (net (code "15") (name "Net-(LED6-K)") (class "Default")
      (node (ref "LED6") (pin "1") (pinfunction "K_1") (pintype "input"))
      (node (ref "R11") (pin "2") (pinfunction "2_2") (pintype "input"))
    )
    (net (code "16") (name "Net-(LED7--)") (class "Default")
      (node (ref "LED7") (pin "1") (pinfunction "-_1") (pintype "input"))
      (node (ref "R10") (pin "2") (pinfunction "2_2") (pintype "input"))
    )
    (net (code "17") (name "Net-(LED8-K)") (class "Default")
      (node (ref "LED8") (pin "1") (pinfunction "K_1") (pintype "input"))
      (node (ref "R13") (pin "2") (pinfunction "2_2") (pintype "input"))
    )
    (net (code "18") (name "Net-(LED9--)") (class "Default")
      (node (ref "LED9") (pin "1") (pinfunction "-_1") (pintype "input"))
      (node (ref "R12") (pin "2") (pinfunction "2_2") (pintype "input"))
    )
    (net (code "19") (name "Net-(LED10-K)") (class "Default")
      (node (ref "LED10") (pin "1") (pinfunction "K_1") (pintype "input"))
      (node (ref "R15") (pin "2") (pinfunction "2_2") (pintype "input"))
    )
    (net (code "20") (name "Net-(LED11--)") (class "Default")
      (node (ref "LED11") (pin "1") (pinfunction "-_1") (pintype "input"))
      (node (ref "R14") (pin "2") (pinfunction "2_2") (pintype "input"))
    )
    (net (code "21") (name "Net-(LED12-K)") (class "Default")
      (node (ref "LED12") (pin "1") (pinfunction "K_1") (pintype "input"))
      (node (ref "R9") (pin "2") (pinfunction "2_2") (pintype "input"))
    )
    (net (code "22") (name "Net-(P2-Pad2)") (class "Default")
      (node (ref "P2") (pin "2") (pinfunction "2_2") (pintype "input"))
      (node (ref "R16") (pin "2") (pinfunction "2_2") (pintype "input"))
    )
    (net (code "23") (name "Net-(P2-Pad3)") (class "Default")
      (node (ref "P2") (pin "3") (pinfunction "3_3") (pintype "input"))
      (node (ref "R17") (pin "2") (pinfunction "2_2") (pintype "input"))
    )
    (net (code "24") (name "Net-(P2-Pad5)") (class "Default")
      (node (ref "P2") (pin "5") (pinfunction "5_5") (pintype "input"))
      (node (ref "R18") (pin "2") (pinfunction "2_2") (pintype "input"))
    )
    (net (code "25") (name "Net-(P2-Pad6)") (class "Default")
      (node (ref "P2") (pin "6") (pinfunction "6_6") (pintype "input"))
      (node (ref "R19") (pin "2") (pinfunction "2_2") (pintype "input"))
    )
    (net (code "26") (name "Net-(P2-Pad7)") (class "Default")
      (node (ref "P2") (pin "7") (pinfunction "7_7") (pintype "input"))
      (node (ref "R20") (pin "1") (pinfunction "1_1") (pintype "input"))
    )
    (net (code "27") (name "Net-(P2-Pad8)") (class "Default")
      (node (ref "P2") (pin "8") (pinfunction "8_8") (pintype "input"))
      (node (ref "R21") (pin "1") (pinfunction "1_1") (pintype "input"))
    )
    (net (code "28") (name "Net-(P2-Pad10)") (class "Default")
      (node (ref "P2") (pin "10") (pinfunction "10_10") (pintype "input"))
      (node (ref "R22") (pin "1") (pinfunction "1_1") (pintype "input"))
    )
    (net (code "29") (name "Net-(P2-Pad11)") (class "Default")
      (node (ref "P2") (pin "11") (pinfunction "11_11") (pintype "input"))
      (node (ref "R23") (pin "1") (pinfunction "1_1") (pintype "input"))
    )
    (net (code "30") (name "Net-(U1-RESET#)") (class "Default")
      (node (ref "C15") (pin "1") (pinfunction "1_1") (pintype "input"))
      (node (ref "R27") (pin "2") (pinfunction "2_2") (pintype "input"))
      (node (ref "U1") (pin "3") (pinfunction "RESET#_3") (pintype "unspecified"))
    )
    (net (code "31") (name "Net-(U1-SCL)") (class "Default")
      (node (ref "R26") (pin "1") (pinfunction "1_1") (pintype "input"))
      (node (ref "U1") (pin "22") (pinfunction "SCL_22") (pintype "unspecified"))
    )
    (net (code "32") (name "Net-(U1-SDA)") (class "Default")
      (node (ref "R25") (pin "1") (pinfunction "1_1") (pintype "input"))
      (node (ref "U1") (pin "23") (pinfunction "SDA_23") (pintype "unspecified"))
    )
    (net (code "33") (name "Net-(USB1-CC1)") (class "Default")
      (node (ref "R2") (pin "2") (pinfunction "2_2") (pintype "input"))
      (node (ref "USB1") (pin "A5") (pinfunction "CC1_A5") (pintype "unspecified"))
    )
    (net (code "34") (name "Net-(USB1-CC2)") (class "Default")
      (node (ref "R1") (pin "1") (pinfunction "1_1") (pintype "input"))
      (node (ref "USB1") (pin "B5") (pinfunction "CC2_B5") (pintype "unspecified"))
    )
    (net (code "35") (name "RESET") (class "Default")
      (node (ref "C7") (pin "1") (pinfunction "1_1") (pintype "unspecified"))
      (node (ref "R3") (pin "1") (pinfunction "1_1") (pintype "input"))
      (node (ref "U3") (pin "7") (pinfunction "RESET_7") (pintype "unspecified"))
    )
    (net (code "36") (name "RXD0") (class "Default")
      (node (ref "R10") (pin "1") (pinfunction "1_1") (pintype "input"))
      (node (ref "R17") (pin "1") (pinfunction "1_1") (pintype "input"))
      (node (ref "U3") (pin "31") (pinfunction "RXD0_31") (pintype "unspecified"))
    )
    (net (code "37") (name "RXD1") (class "Default")
      (node (ref "R19") (pin "1") (pinfunction "1_1") (pintype "input"))
      (node (ref "R8") (pin "1") (pinfunction "1_1") (pintype "input"))
      (node (ref "U3") (pin "13") (pinfunction "RXD1_13") (pintype "unspecified"))
    )
    (net (code "38") (name "RXD2") (class "Default")
      (node (ref "R12") (pin "1") (pinfunction "1_1") (pintype "input"))
      (node (ref "R22") (pin "2") (pinfunction "2_2") (pintype "input"))
      (node (ref "U3") (pin "22") (pinfunction "RXD2_22") (pintype "unspecified"))
    )
    (net (code "39") (name "RXD3") (class "Default")
      (node (ref "R14") (pin "1") (pinfunction "1_1") (pintype "input"))
      (node (ref "R20") (pin "2") (pinfunction "2_2") (pintype "input"))
      (node (ref "U3") (pin "38") (pinfunction "RXD3_38") (pintype "unspecified"))
    )
    (net (code "40") (name "RX_LED") (class "Default")
      (node (ref "R6") (pin "1") (pinfunction "1_1") (pintype "input"))
      (node (ref "U3") (pin "16") (pinfunction "RX_S_16") (pintype "unspecified"))
    )
    (net (code "41") (name "SC0") (class "Default")
      (node (ref "R28") (pin "1") (pinfunction "1_1") (pintype "input"))
      (node (ref "U1") (pin "5") (pinfunction "SC0_5") (pintype "unspecified"))
    )
    (net (code "42") (name "SC1") (class "Default")
      (node (ref "R30") (pin "1") (pinfunction "1_1") (pintype "input"))
      (node (ref "U1") (pin "7") (pinfunction "SC1_7") (pintype "unspecified"))
    )
    (net (code "43") (name "SC2") (class "Default")
      (node (ref "R32") (pin "1") (pinfunction "1_1") (pintype "input"))
      (node (ref "U1") (pin "9") (pinfunction "SC2_9") (pintype "unspecified"))
    )
    (net (code "44") (name "SC3") (class "Default")
      (node (ref "R34") (pin "1") (pinfunction "1_1") (pintype "input"))
      (node (ref "U1") (pin "11") (pinfunction "SC3_11") (pintype "unspecified"))
    )
    (net (code "45") (name "SC4") (class "Default")
      (node (ref "R42") (pin "1") (pinfunction "1_1") (pintype "input"))
      (node (ref "U1") (pin "14") (pinfunction "SC4_14") (pintype "unspecified"))
    )
    (net (code "46") (name "SC5") (class "Default")
      (node (ref "R40") (pin "1") (pinfunction "1_1") (pintype "input"))
      (node (ref "U1") (pin "16") (pinfunction "SC5_16") (pintype "unspecified"))
    )
    (net (code "47") (name "SC6") (class "Default")
      (node (ref "R38") (pin "1") (pinfunction "1_1") (pintype "input"))
      (node (ref "U1") (pin "18") (pinfunction "SC6_18") (pintype "unspecified"))
    )
    (net (code "48") (name "SC7") (class "Default")
      (node (ref "R36") (pin "1") (pinfunction "1_1") (pintype "input"))
      (node (ref "U1") (pin "20") (pinfunction "SC7_20") (pintype "unspecified"))
    )
    (net (code "49") (name "SD0") (class "Default")
      (node (ref "R29") (pin "1") (pinfunction "1_1") (pintype "input"))
      (node (ref "U1") (pin "4") (pinfunction "SD0_4") (pintype "unspecified"))
    )
    (net (code "50") (name "SD1") (class "Default")
      (node (ref "R31") (pin "1") (pinfunction "1_1") (pintype "input"))
      (node (ref "U1") (pin "6") (pinfunction "SD1_6") (pintype "unspecified"))
    )
    (net (code "51") (name "SD2") (class "Default")
      (node (ref "R33") (pin "1") (pinfunction "1_1") (pintype "input"))
      (node (ref "U1") (pin "8") (pinfunction "SD2_8") (pintype "unspecified"))
    )
    (net (code "52") (name "SD3") (class "Default")
      (node (ref "R35") (pin "1") (pinfunction "1_1") (pintype "input"))
      (node (ref "U1") (pin "10") (pinfunction "SD3_10") (pintype "unspecified"))
    )
    (net (code "53") (name "SD4") (class "Default")
      (node (ref "R43") (pin "1") (pinfunction "1_1") (pintype "input"))
      (node (ref "U1") (pin "13") (pinfunction "SD4_13") (pintype "unspecified"))
    )
    (net (code "54") (name "SD5") (class "Default")
      (node (ref "R41") (pin "1") (pinfunction "1_1") (pintype "input"))
      (node (ref "U1") (pin "15") (pinfunction "SD5_15") (pintype "unspecified"))
    )
    (net (code "55") (name "SD6") (class "Default")
      (node (ref "R39") (pin "1") (pinfunction "1_1") (pintype "input"))
      (node (ref "U1") (pin "17") (pinfunction "SD6_17") (pintype "unspecified"))
    )
    (net (code "56") (name "SD7") (class "Default")
      (node (ref "R37") (pin "1") (pinfunction "1_1") (pintype "input"))
      (node (ref "U1") (pin "19") (pinfunction "SD7_19") (pintype "unspecified"))
    )
    (net (code "57") (name "SPI_CS0N") (class "Default")
      (node (ref "U4") (pin "15") (pinfunction "Y0_15") (pintype "unspecified"))
    )
    (net (code "58") (name "SPI_CS1N") (class "Default")
      (node (ref "U4") (pin "14") (pinfunction "Y1_14") (pintype "unspecified"))
    )
    (net (code "59") (name "SPI_CS2N") (class "Default")
      (node (ref "U4") (pin "13") (pinfunction "Y2_13") (pintype "unspecified"))
    )
    (net (code "60") (name "SPI_CS3N") (class "Default")
      (node (ref "U4") (pin "12") (pinfunction "Y3_12") (pintype "unspecified"))
    )
    (net (code "61") (name "SPI_CS4N") (class "Default")
      (node (ref "U4") (pin "11") (pinfunction "Y4_11") (pintype "unspecified"))
    )
    (net (code "62") (name "SPI_CS5N") (class "Default")
      (node (ref "U4") (pin "10") (pinfunction "Y5_10") (pintype "unspecified"))
    )
    (net (code "63") (name "SPI_CS6N") (class "Default")
      (node (ref "U4") (pin "9") (pinfunction "Y6_9") (pintype "unspecified"))
    )
    (net (code "64") (name "SPI_CS7N_HIGHT") (class "Default")
      (node (ref "U4") (pin "7") (pinfunction "Y7_7") (pintype "unspecified"))
    )
    (net (code "65") (name "SPI_CSN") (class "Default")
      (node (ref "R24") (pin "1") (pinfunction "1_1") (pintype "input"))
      (node (ref "U4") (pin "6") (pinfunction "G1_6") (pintype "unspecified"))
    )
    (net (code "66") (name "TEST") (class "Default")
      (node (ref "R4") (pin "2") (pinfunction "2_2") (pintype "input"))
      (node (ref "U3") (pin "44") (pinfunction "TEST_44") (pintype "unspecified"))
    )
    (net (code "67") (name "TXD0") (class "Default")
      (node (ref "R11") (pin "1") (pinfunction "1_1") (pintype "input"))
      (node (ref "R16") (pin "1") (pinfunction "1_1") (pintype "input"))
      (node (ref "U3") (pin "30") (pinfunction "TXD0_30") (pintype "unspecified"))
    )
    (net (code "68") (name "TXD1") (class "Default")
      (node (ref "R18") (pin "1") (pinfunction "1_1") (pintype "input"))
      (node (ref "R9") (pin "1") (pinfunction "1_1") (pintype "input"))
      (node (ref "U3") (pin "12") (pinfunction "TXD1_12") (pintype "unspecified"))
    )
    (net (code "69") (name "TXD2") (class "Default")
      (node (ref "R13") (pin "1") (pinfunction "1_1") (pintype "input"))
      (node (ref "R23") (pin "2") (pinfunction "2_2") (pintype "input"))
      (node (ref "U3") (pin "21") (pinfunction "TXD2_21") (pintype "unspecified"))
    )
    (net (code "70") (name "TXD3") (class "Default")
      (node (ref "R15") (pin "1") (pinfunction "1_1") (pintype "input"))
      (node (ref "R21") (pin "2") (pinfunction "2_2") (pintype "input"))
      (node (ref "U3") (pin "37") (pinfunction "TXD3_37") (pintype "unspecified"))
    )
    (net (code "71") (name "TX_LED") (class "Default")
      (node (ref "R5") (pin "1") (pinfunction "1_1") (pintype "input"))
      (node (ref "U3") (pin "15") (pinfunction "TX_S_15") (pintype "unspecified"))
    )
    (net (code "72") (name "UD+") (class "Default")
      (node (ref "U3") (pin "43") (pinfunction "UD+_43") (pintype "unspecified"))
      (node (ref "USB1") (pin "A6") (pinfunction "DP1_A6") (pintype "unspecified"))
      (node (ref "USB1") (pin "B6") (pinfunction "DP2_B6") (pintype "unspecified"))
    )
    (net (code "73") (name "UD-") (class "Default")
      (node (ref "U3") (pin "42") (pinfunction "UD-_42") (pintype "unspecified"))
      (node (ref "USB1") (pin "A7") (pinfunction "DN1_A7") (pintype "unspecified"))
      (node (ref "USB1") (pin "B7") (pinfunction "DN2_B7") (pintype "unspecified"))
    )
    (net (code "74") (name "VBUS") (class "Default")
      (node (ref "F1") (pin "1") (pinfunction "1_1") (pintype "unspecified"))
      (node (ref "USB1") (pin "A4") (pinfunction "VBUS_A4") (pintype "unspecified"))
      (node (ref "USB1") (pin "A9") (pinfunction "VBUS_A9") (pintype "unspecified"))
      (node (ref "USB1") (pin "B4") (pinfunction "VBUS_B4") (pintype "unspecified"))
      (node (ref "USB1") (pin "B9") (pinfunction "VBUS_B9") (pintype "unspecified"))
    )
    (net (code "75") (name "VCC") (class "Default")
      (node (ref "C10") (pin "1") (pinfunction "1_1") (pintype "unspecified"))
      (node (ref "C11") (pin "1") (pinfunction "1_1") (pintype "unspecified"))
      (node (ref "C2") (pin "2") (pinfunction "2_2") (pintype "unspecified"))
      (node (ref "C3") (pin "1") (pinfunction "1_1") (pintype "unspecified"))
      (node (ref "C8") (pin "1") (pinfunction "1_1") (pintype "unspecified"))
      (node (ref "C9") (pin "1") (pinfunction "1_1") (pintype "unspecified"))
      (node (ref "LED1") (pin "2") (pinfunction "A_2") (pintype "input"))
      (node (ref "LED10") (pin "2") (pinfunction "A_2") (pintype "input"))
      (node (ref "LED11") (pin "2") (pinfunction "+_2") (pintype "input"))
      (node (ref "LED12") (pin "2") (pinfunction "A_2") (pintype "input"))
      (node (ref "LED2") (pin "2") (pinfunction "+_2") (pintype "input"))
      (node (ref "LED3") (pin "2") (pinfunction "A_2") (pintype "input"))
      (node (ref "LED5") (pin "2") (pinfunction "+_2") (pintype "input"))
      (node (ref "LED6") (pin "2") (pinfunction "A_2") (pintype "input"))
      (node (ref "LED7") (pin "2") (pinfunction "+_2") (pintype "input"))
      (node (ref "LED8") (pin "2") (pinfunction "A_2") (pintype "input"))
      (node (ref "LED9") (pin "2") (pinfunction "+_2") (pintype "input"))
      (node (ref "R3") (pin "2") (pinfunction "2_2") (pintype "input"))
      (node (ref "U1") (pin "24") (pinfunction "VCC_24") (pintype "unspecified"))
      (node (ref "U2") (pin "2") (pinfunction "VOUT(TAB)_2") (pintype "unspecified"))
      (node (ref "U3") (pin "24") (pinfunction "VCC_24") (pintype "unspecified"))
      (node (ref "U3") (pin "36") (pinfunction "VCC_36") (pintype "unspecified"))
      (node (ref "U3") (pin "48") (pinfunction "VCC_48") (pintype "unspecified"))
      (node (ref "U3") (pin "9") (pinfunction "VCC_9") (pintype "unspecified"))
      (node (ref "U5") (pin "1") (pinfunction "1_1") (pintype "unspecified"))
      (node (ref "U5") (pin "2") (pinfunction "2_2") (pintype "unspecified"))
      (node (ref "U5") (pin "3") (pinfunction "3_3") (pintype "unspecified"))
    )
    (net (code "76") (name "XI") (class "Default")
      (node (ref "C13") (pin "1") (pinfunction "1_1") (pintype "input"))
      (node (ref "U3") (pin "5") (pinfunction "XI_5") (pintype "unspecified"))
      (node (ref "X2") (pin "1") (pinfunction "1_1") (pintype "input"))
    )
    (net (code "77") (name "XO") (class "Default")
      (node (ref "C12") (pin "1") (pinfunction "1_1") (pintype "input"))
      (node (ref "U3") (pin "6") (pinfunction "XO_6") (pintype "unspecified"))
      (node (ref "X2") (pin "3") (pinfunction "3_3") (pintype "input"))
    )
    (net (code "78") (name "unconnected-(U3-ACT-Pad14)") (class "Default")
      (node (ref "U3") (pin "14") (pinfunction "ACT_14") (pintype "unspecified+no_connect"))
    )
    (net (code "79") (name "unconnected-(U3-CTS0{slash}GPIO0-Pad41)") (class "Default")
      (node (ref "U3") (pin "41") (pinfunction "CTS0/GPIO0_41") (pintype "unspecified+no_connect"))
    )
    (net (code "80") (name "unconnected-(U3-CTS1{slash}GPIO2-Pad10)") (class "Default")
      (node (ref "U3") (pin "10") (pinfunction "CTS1/GPIO2_10") (pintype "unspecified+no_connect"))
    )
    (net (code "81") (name "unconnected-(U3-CTS2{slash}GPIO4-Pad26)") (class "Default")
      (node (ref "U3") (pin "26") (pinfunction "CTS2/GPIO4_26") (pintype "unspecified+no_connect"))
    )
    (net (code "82") (name "unconnected-(U3-CTS3{slash}GPIO6-Pad46)") (class "Default")
      (node (ref "U3") (pin "46") (pinfunction "CTS3/GPIO6_46") (pintype "unspecified+no_connect"))
    )
    (net (code "83") (name "unconnected-(U3-DCD0{slash}_GPIO12-Pad33)") (class "Default")
      (node (ref "U3") (pin "33") (pinfunction "DCD0/_GPIO12_33") (pintype "unspecified+no_connect"))
    )
    (net (code "84") (name "unconnected-(U3-DCD1{slash}_GPIO15-Pad28)") (class "Default")
      (node (ref "U3") (pin "28") (pinfunction "DCD1/_GPIO15_28") (pintype "unspecified+no_connect"))
    )
    (net (code "85") (name "unconnected-(U3-DCD2-Pad4)") (class "Default")
      (node (ref "U3") (pin "4") (pinfunction "DCD2_4") (pintype "unspecified+no_connect"))
    )
    (net (code "86") (name "unconnected-(U3-DSR0{slash}_GPIO14-Pad29)") (class "Default")
      (node (ref "U3") (pin "29") (pinfunction "DSR0/_GPIO14_29") (pintype "unspecified+no_connect"))
    )
    (net (code "87") (name "unconnected-(U3-DSR1-Pad17)") (class "Default")
      (node (ref "U3") (pin "17") (pinfunction "DSR1_17") (pintype "unspecified+no_connect"))
    )
    (net (code "88") (name "unconnected-(U3-DSR2-Pad2)") (class "Default")
      (node (ref "U3") (pin "2") (pinfunction "DSR2_2") (pintype "unspecified+no_connect"))
    )
    (net (code "89") (name "unconnected-(U3-NC-Pad1)") (class "Default")
      (node (ref "U3") (pin "1") (pinfunction "NC_1") (pintype "unspecified+no_connect"))
    )
    (net (code "90") (name "unconnected-(U3-RI0{slash}_GPIO13-Pad32)") (class "Default")
      (node (ref "U3") (pin "32") (pinfunction "RI0/_GPIO13_32") (pintype "unspecified+no_connect"))
    )
    (net (code "91") (name "unconnected-(U3-RI1-Pad25)") (class "Default")
      (node (ref "U3") (pin "25") (pinfunction "RI1_25") (pintype "unspecified+no_connect"))
    )
    (net (code "92") (name "unconnected-(U3-RI2-Pad3)") (class "Default")
      (node (ref "U3") (pin "3") (pinfunction "RI2_3") (pintype "unspecified+no_connect"))
    )
    (net (code "93") (name "unconnected-(U3-RTS0{slash}GPIO1-Pad40)") (class "Default")
      (node (ref "U3") (pin "40") (pinfunction "RTS0/GPIO1_40") (pintype "unspecified+no_connect"))
    )
    (net (code "94") (name "unconnected-(U3-RTS1{slash}GPIO3-Pad11)") (class "Default")
      (node (ref "U3") (pin "11") (pinfunction "RTS1/GPIO3_11") (pintype "unspecified+no_connect"))
    )
    (net (code "95") (name "unconnected-(U3-RTS2{slash}GPIO5-Pad27)") (class "Default")
      (node (ref "U3") (pin "27") (pinfunction "RTS2/GPIO5_27") (pintype "unspecified+no_connect"))
    )
    (net (code "96") (name "unconnected-(U3-RTS3{slash}GPIO7-Pad45)") (class "Default")
      (node (ref "U3") (pin "45") (pinfunction "RTS3/GPIO7_45") (pintype "unspecified+no_connect"))
    )
    (net (code "97") (name "unconnected-(U3-TNOW0{slash}GPIO8-Pad39)") (class "Default")
      (node (ref "U3") (pin "39") (pinfunction "TNOW0/GPIO8_39") (pintype "unspecified+no_connect"))
    )
    (net (code "98") (name "unconnected-(U3-TNOW1{slash}GPIO9-Pad18)") (class "Default")
      (node (ref "U3") (pin "18") (pinfunction "TNOW1/GPIO9_18") (pintype "unspecified+no_connect"))
    )
    (net (code "99") (name "unconnected-(U3-TNOW2{slash}GPIO10-Pad19)") (class "Default")
      (node (ref "U3") (pin "19") (pinfunction "TNOW2/GPIO10_19") (pintype "unspecified+no_connect"))
    )
    (net (code "100") (name "unconnected-(U3-TNOW3{slash}_DTR3{slash}_GPIO11-Pad34)") (class "Default")
      (node (ref "U3") (pin "34") (pinfunction "TNOW3/_DTR3/_GPIO11_34") (pintype "unspecified+no_connect"))
    )
    (net (code "101") (name "unconnected-(USB1-SUB1-PadA8)") (class "Default")
      (node (ref "USB1") (pin "A8") (pinfunction "SUB1_A8") (pintype "unspecified+no_connect"))
    )
    (net (code "102") (name "unconnected-(USB1-SUB2-PadB8)") (class "Default")
      (node (ref "USB1") (pin "B8") (pinfunction "SUB2_B8") (pintype "unspecified+no_connect"))
    )
  )
)
